# Sheet4.net
KiCad netlist of a schematic drawn in Altium Designer
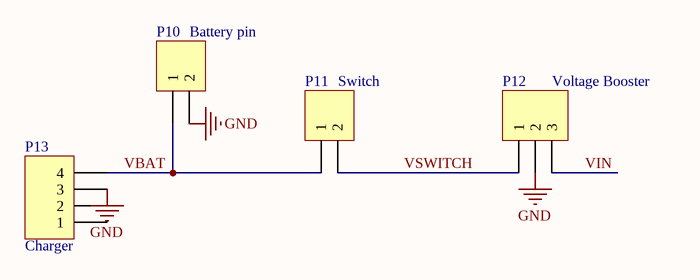
[diagram p0: Sheet4.SchDoc]

(export (version "E")
  (design (tool "Eeschema 10.0.6"))
  (components
    (comp (ref "P10")
      (value "Battery pin")
      (footprint "HDR1X2")
      (description "Header, 2-Pin")
      (fields (field (name "PUBLISHER") "Altium Limited"))
      (libsource (lib "Miscellaneous Connectors") (part "Header 2"))
    )
    (comp (ref "P11")
      (value "Switch")
      (footprint "HDR1X2")
      (description "Header, 2-Pin")
      (fields (field (name "PUBLISHER") "Altium Limited"))
      (libsource (lib "Miscellaneous Connectors") (part "Header 2"))
    )
    (comp (ref "P12")
      (value "Voltage Booster")
      (footprint "Voltage Regulator")
      (description "Header, 3-Pin")
      (fields (field (name "PUBLISHER") "Altium Limited"))
      (libsource (lib "Miscellaneous Connectors") (part "Header 3"))
    )
    (comp (ref "P13")
      (value "Charger")
      (footprint "HDR1X4")
      (description "Header, 4-Pin")
      (fields (field (name "PUBLISHER") "Altium Limited"))
      (libsource (lib "Miscellaneous Connectors") (part "Header 4"))
    )
  )
  (nets
    (net (code "1") (name "/VBAT") (class "Default")
      (node (ref "P10") (pin "1") (pinfunction "1_1") (pintype "passive"))
      (node (ref "P11") (pin "1") (pinfunction "1_1") (pintype "passive"))
      (node (ref "P13") (pin "4") (pinfunction "4_4") (pintype "passive"))
    )
    (net (code "2") (name "/VIN") (class "Default")
      (node (ref "P12") (pin "3") (pinfunction "3_3") (pintype "passive"))
    )
    (net (code "3") (name "/VSWITCH") (class "Default")
      (node (ref "P11") (pin "2") (pinfunction "2_2") (pintype "passive"))
      (node (ref "P12") (pin "1") (pinfunction "1_1") (pintype "passive"))
    )
    (net (code "4") (name "GND") (class "Default")
      (node (ref "P10") (pin "2") (pinfunction "2_2") (pintype "passive"))
      (node (ref "P12") (pin "2") (pinfunction "2_2") (pintype "passive"))
      (node (ref "P13") (pin "3") (pinfunction "3_3") (pintype "passive"))
    )
    (net (code "5") (name "unconnected-(P13-Pad1)") (class "Default")
      (node (ref "P13") (pin "1") (pinfunction "1_1") (pintype "passive"))
    )
    (net (code "6") (name "unconnected-(P13-Pad2)") (class "Default")
      (node (ref "P13") (pin "2") (pinfunction "2_2") (pintype "passive"))
    )
  )
)
